# sistema_min.net
KiCad netlist of a schematic drawn in EAGLE
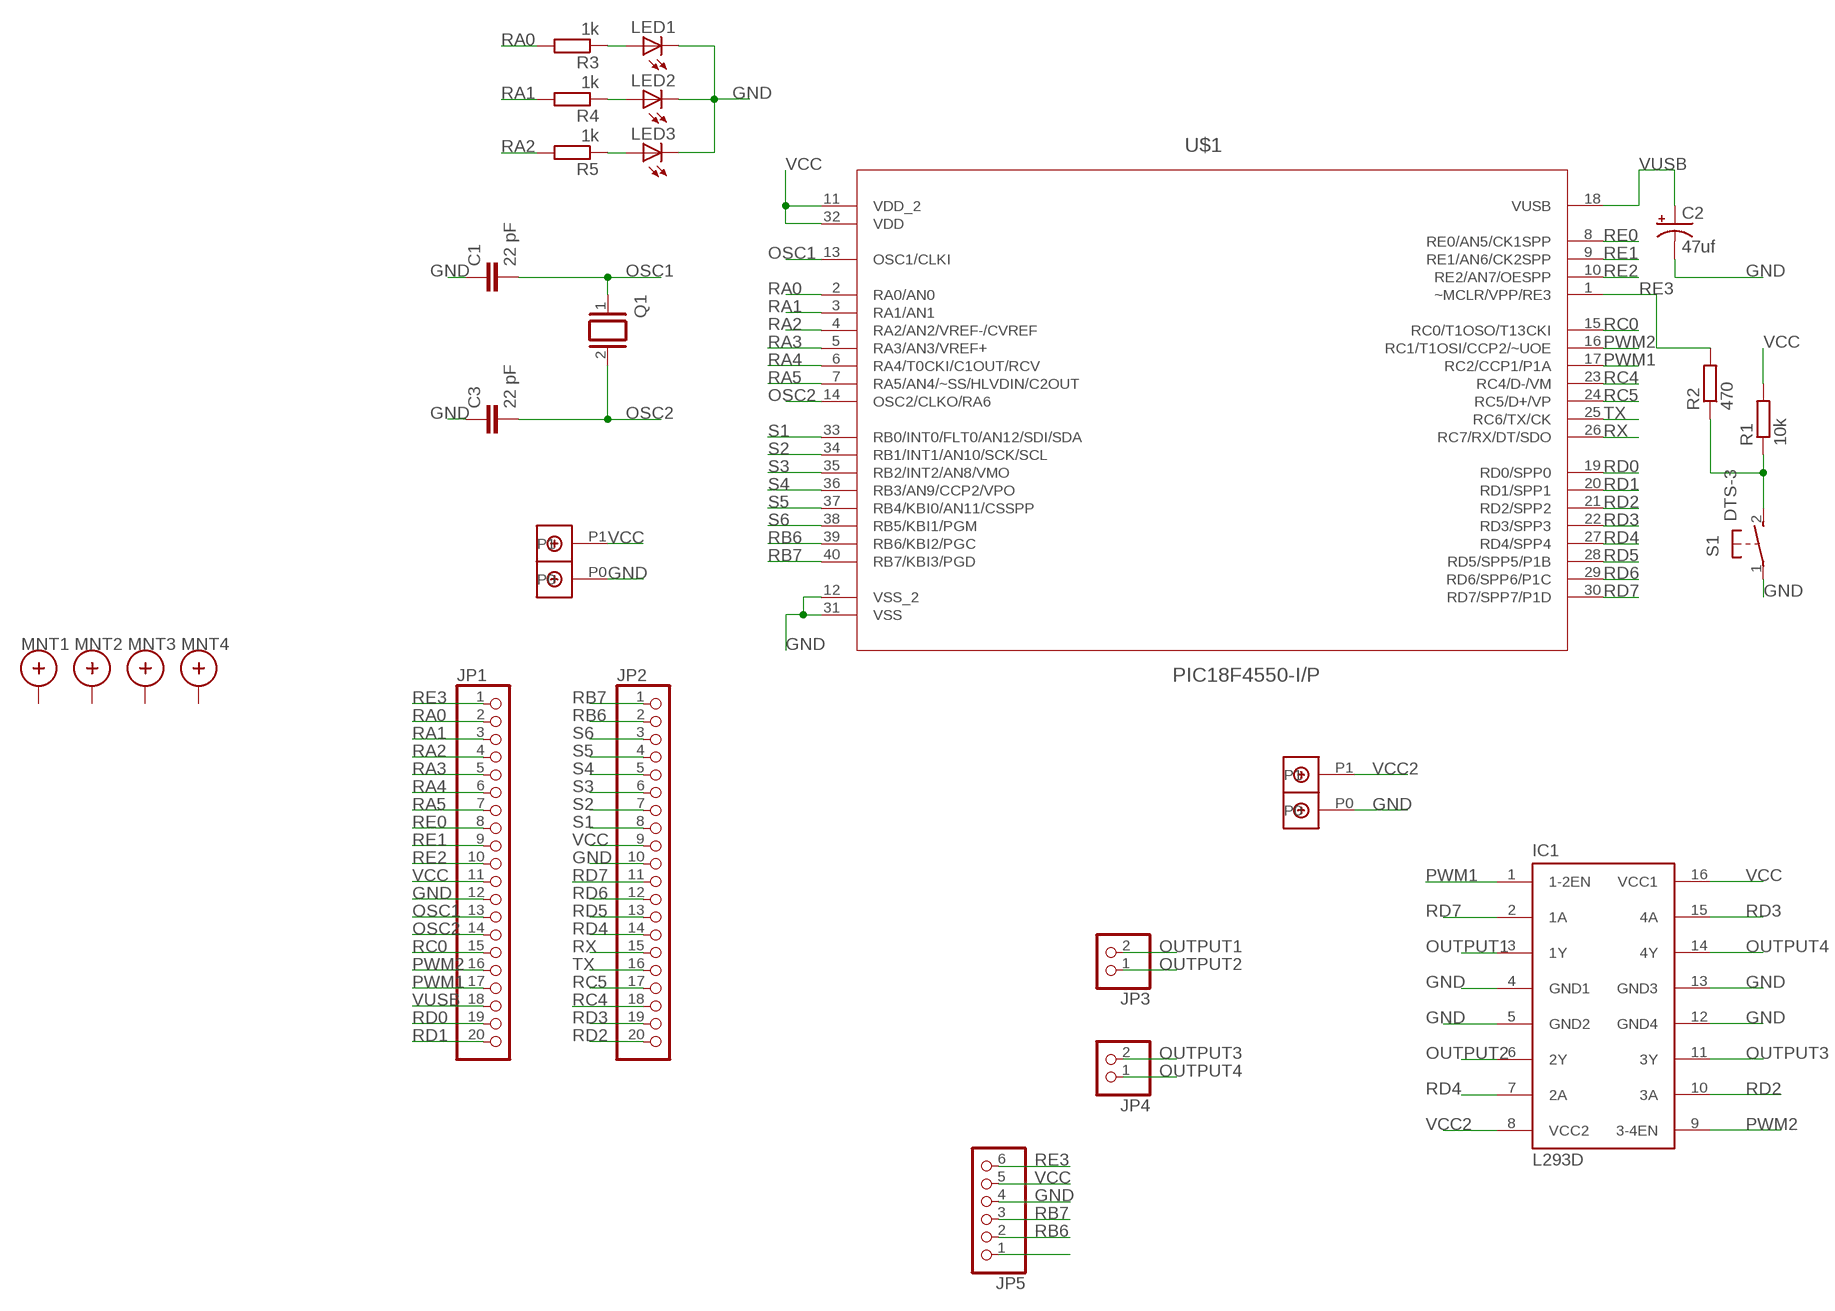
[diagram p0: schematic, sheet 1]

(export (version "E")
  (design (tool "Eeschema 10.0.6"))
  (components
    (comp (ref "C1")
      (value "22 pF")
      (footprint "eagle-import:C050-025X075")
      (libsource (lib "eagle-import") (part "C-EU050-025X075"))
    )
    (comp (ref "C2")
      (value "47uf")
      (footprint "eagle-import:E5-10,5")
      (libsource (lib "eagle-import") (part "CPOL-USE5-10.5"))
    )
    (comp (ref "C3")
      (value "22 pF")
      (footprint "eagle-import:C050-025X075")
      (libsource (lib "eagle-import") (part "C-EU050-025X075"))
    )
    (comp (ref "IC1")
      (value "L293D")
      (footprint "eagle-import:DIL16")
      (libsource (lib "eagle-import") (part "L293D"))
    )
    (comp (ref "JP1")
      (value "PINHD-1X20")
      (footprint "eagle-import:1X20")
      (libsource (lib "eagle-import") (part "PINHD-1X20"))
    )
    (comp (ref "JP2")
      (value "PINHD-1X20")
      (footprint "eagle-import:1X20")
      (libsource (lib "eagle-import") (part "PINHD-1X20"))
    )
    (comp (ref "JP3")
      (value "PINHD-1X2")
      (footprint "eagle-import:1X02")
      (libsource (lib "eagle-import") (part "PINHD-1X2"))
    )
    (comp (ref "JP4")
      (value "PINHD-1X2")
      (footprint "eagle-import:1X02")
      (libsource (lib "eagle-import") (part "PINHD-1X2"))
    )
    (comp (ref "JP5")
      (value "PINHD-1X6")
      (footprint "eagle-import:1X06")
      (libsource (lib "eagle-import") (part "PINHD-1X6"))
    )
    (comp (ref "LED1")
      (value "LED3MM")
      (footprint "eagle-import:LED3MM")
      (libsource (lib "eagle-import") (part "LED3MM"))
    )
    (comp (ref "LED2")
      (value "LED3MM")
      (footprint "eagle-import:LED3MM")
      (libsource (lib "eagle-import") (part "LED3MM"))
    )
    (comp (ref "LED3")
      (value "LED3MM")
      (footprint "eagle-import:LED3MM")
      (libsource (lib "eagle-import") (part "LED3MM"))
    )
    (comp (ref "MNT1")
      (value "HOLE_MNT_0.135")
      (footprint "eagle-import:HOLE_MNT_#5-40")
      (libsource (lib "eagle-import") (part "HOLE_MNT_0.135"))
    )
    (comp (ref "MNT2")
      (value "HOLE_MNT_0.135")
      (footprint "eagle-import:HOLE_MNT_#5-40")
      (libsource (lib "eagle-import") (part "HOLE_MNT_0.135"))
    )
    (comp (ref "MNT3")
      (value "HOLE_MNT_0.135")
      (footprint "eagle-import:HOLE_MNT_#5-40")
      (libsource (lib "eagle-import") (part "HOLE_MNT_0.135"))
    )
    (comp (ref "MNT4")
      (value "HOLE_MNT_0.135")
      (footprint "eagle-import:HOLE_MNT_#5-40")
      (libsource (lib "eagle-import") (part "HOLE_MNT_0.135"))
    )
    (comp (ref "Q1")
      (value "XTAL/S")
      (footprint "eagle-import:QS")
      (libsource (lib "eagle-import") (part "XTAL/S"))
    )
    (comp (ref "R1")
      (value "10k")
      (footprint "eagle-import:0204_7")
      (libsource (lib "eagle-import") (part "R-EU_0204/7"))
    )
    (comp (ref "R2")
      (value "470")
      (footprint "eagle-import:0204_7")
      (libsource (lib "eagle-import") (part "R-EU_0204/7"))
    )
    (comp (ref "R3")
      (value "1k")
      (footprint "eagle-import:0204_7")
      (libsource (lib "eagle-import") (part "R-EU_0204/7"))
    )
    (comp (ref "R4")
      (value "1k")
      (footprint "eagle-import:0204_7")
      (libsource (lib "eagle-import") (part "R-EU_0204/7"))
    )
    (comp (ref "R5")
      (value "1k")
      (footprint "eagle-import:0204_7")
      (libsource (lib "eagle-import") (part "R-EU_0204/7"))
    )
    (comp (ref "S1")
      (value "DTS-3")
      (footprint "eagle-import:DTS-3")
      (libsource (lib "eagle-import") (part "DTS-3"))
    )
    (comp (ref "U$1")
      (value "PIC18F4550-I/P")
      (footprint "eagle-import:DIP254P1524X635-40")
      (libsource (lib "eagle-import") (part "PIC18F4550-I/P"))
    )
    (comp (ref "U$2")
      (value "DBCONN-1X2")
      (footprint "eagle-import:DBCONN-1X2")
      (libsource (lib "eagle-import") (part "DBCONN-1X2"))
    )
    (comp (ref "U$3")
      (value "DBCONN-1X2")
      (footprint "eagle-import:DBCONN-1X2")
      (libsource (lib "eagle-import") (part "DBCONN-1X2"))
    )
  )
  (nets
    (net (code "1") (name "/GND") (class "Default")
      (node (ref "C1") (pin "1") (pinfunction "1_1") (pintype "passive"))
      (node (ref "C2") (pin "-") (pinfunction "-_-") (pintype "passive"))
      (node (ref "C3") (pin "1") (pinfunction "1_1") (pintype "passive"))
      (node (ref "IC1") (pin "12") (pinfunction "GND4_12") (pintype "power_in"))
      (node (ref "IC1") (pin "13") (pinfunction "GND3_13") (pintype "power_in"))
      (node (ref "IC1") (pin "4") (pinfunction "GND1_4") (pintype "power_in"))
      (node (ref "IC1") (pin "5") (pinfunction "GND2_5") (pintype "power_in"))
      (node (ref "JP1") (pin "12") (pinfunction "12_12") (pintype "passive"))
      (node (ref "JP2") (pin "10") (pinfunction "10_10") (pintype "passive"))
      (node (ref "JP5") (pin "4") (pinfunction "4_4") (pintype "passive"))
      (node (ref "LED1") (pin "K") (pinfunction "C_K") (pintype "passive"))
      (node (ref "LED2") (pin "K") (pinfunction "C_K") (pintype "passive"))
      (node (ref "LED3") (pin "K") (pinfunction "C_K") (pintype "passive"))
      (node (ref "S1") (pin "1") (pinfunction "1_1") (pintype "passive"))
      (node (ref "U$1") (pin "12") (pinfunction "VSS_2_12") (pintype "power_in"))
      (node (ref "U$1") (pin "31") (pinfunction "VSS_31") (pintype "power_in"))
      (node (ref "U$2") (pin "P0") (pinfunction "P0_P0") (pintype "bidirectional"))
      (node (ref "U$3") (pin "P0") (pinfunction "P0_P0") (pintype "bidirectional"))
    )
    (net (code "2") (name "/OSC1") (class "Default")
      (node (ref "C1") (pin "2") (pinfunction "2_2") (pintype "passive"))
      (node (ref "JP1") (pin "13") (pinfunction "13_13") (pintype "passive"))
      (node (ref "Q1") (pin "1") (pinfunction "1_1") (pintype "passive"))
      (node (ref "U$1") (pin "13") (pinfunction "OSC1/CLKI_13") (pintype "input"))
    )
    (net (code "3") (name "/OSC2") (class "Default")
      (node (ref "C3") (pin "2") (pinfunction "2_2") (pintype "passive"))
      (node (ref "JP1") (pin "14") (pinfunction "14_14") (pintype "passive"))
      (node (ref "Q1") (pin "2") (pinfunction "2_2") (pintype "passive"))
      (node (ref "U$1") (pin "14") (pinfunction "OSC2/CLKO/RA6_14") (pintype "bidirectional"))
    )
    (net (code "4") (name "/OUTPUT1") (class "Default")
      (node (ref "IC1") (pin "3") (pinfunction "1Y_3") (pintype "output"))
      (node (ref "JP3") (pin "2") (pinfunction "2_2") (pintype "passive"))
    )
    (net (code "5") (name "/OUTPUT2") (class "Default")
      (node (ref "IC1") (pin "6") (pinfunction "2Y_6") (pintype "output"))
      (node (ref "JP3") (pin "1") (pinfunction "1_1") (pintype "passive"))
    )
    (net (code "6") (name "/OUTPUT3") (class "Default")
      (node (ref "IC1") (pin "11") (pinfunction "3Y_11") (pintype "output"))
      (node (ref "JP4") (pin "2") (pinfunction "2_2") (pintype "passive"))
    )
    (net (code "7") (name "/OUTPUT4") (class "Default")
      (node (ref "IC1") (pin "14") (pinfunction "4Y_14") (pintype "output"))
      (node (ref "JP4") (pin "1") (pinfunction "1_1") (pintype "passive"))
    )
    (net (code "8") (name "/PWM1") (class "Default")
      (node (ref "IC1") (pin "1") (pinfunction "1-2EN_1") (pintype "input"))
      (node (ref "JP1") (pin "17") (pinfunction "17_17") (pintype "passive"))
      (node (ref "U$1") (pin "17") (pinfunction "RC2/CCP1/P1A_17") (pintype "bidirectional"))
    )
    (net (code "9") (name "/PWM2") (class "Default")
      (node (ref "IC1") (pin "9") (pinfunction "3-4EN_9") (pintype "input"))
      (node (ref "JP1") (pin "16") (pinfunction "16_16") (pintype "passive"))
      (node (ref "U$1") (pin "16") (pinfunction "RC1/T1OSI/CCP2/~{UOE}_16") (pintype "bidirectional"))
    )
    (net (code "10") (name "/RA0") (class "Default")
      (node (ref "JP1") (pin "2") (pinfunction "2_2") (pintype "passive"))
      (node (ref "R3") (pin "2") (pinfunction "2_2") (pintype "passive"))
      (node (ref "U$1") (pin "2") (pinfunction "RA0/AN0_2") (pintype "bidirectional"))
    )
    (net (code "11") (name "/RA1") (class "Default")
      (node (ref "JP1") (pin "3") (pinfunction "3_3") (pintype "passive"))
      (node (ref "R4") (pin "2") (pinfunction "2_2") (pintype "passive"))
      (node (ref "U$1") (pin "3") (pinfunction "RA1/AN1_3") (pintype "bidirectional"))
    )
    (net (code "12") (name "/RA2") (class "Default")
      (node (ref "JP1") (pin "4") (pinfunction "4_4") (pintype "passive"))
      (node (ref "R5") (pin "2") (pinfunction "2_2") (pintype "passive"))
      (node (ref "U$1") (pin "4") (pinfunction "RA2/AN2/VREF-/CVREF_4") (pintype "bidirectional"))
    )
    (net (code "13") (name "/RA3") (class "Default")
      (node (ref "JP1") (pin "5") (pinfunction "5_5") (pintype "passive"))
      (node (ref "U$1") (pin "5") (pinfunction "RA3/AN3/VREF+_5") (pintype "bidirectional"))
    )
    (net (code "14") (name "/RA4") (class "Default")
      (node (ref "JP1") (pin "6") (pinfunction "6_6") (pintype "passive"))
      (node (ref "U$1") (pin "6") (pinfunction "RA4/T0CKI/C1OUT/RCV_6") (pintype "bidirectional"))
    )
    (net (code "15") (name "/RA5") (class "Default")
      (node (ref "JP1") (pin "7") (pinfunction "7_7") (pintype "passive"))
      (node (ref "U$1") (pin "7") (pinfunction "RA5/AN4/~{SS/HLVDIN/C2OUT}_7") (pintype "bidirectional"))
    )
    (net (code "16") (name "/RB6") (class "Default")
      (node (ref "JP2") (pin "2") (pinfunction "2_2") (pintype "passive"))
      (node (ref "JP5") (pin "2") (pinfunction "2_2") (pintype "passive"))
      (node (ref "U$1") (pin "39") (pinfunction "RB6/KBI2/PGC_39") (pintype "bidirectional"))
    )
    (net (code "17") (name "/RB7") (class "Default")
      (node (ref "JP2") (pin "1") (pinfunction "1_1") (pintype "passive"))
      (node (ref "JP5") (pin "3") (pinfunction "3_3") (pintype "passive"))
      (node (ref "U$1") (pin "40") (pinfunction "RB7/KBI3/PGD_40") (pintype "bidirectional"))
    )
    (net (code "18") (name "/RC0") (class "Default")
      (node (ref "JP1") (pin "15") (pinfunction "15_15") (pintype "passive"))
      (node (ref "U$1") (pin "15") (pinfunction "RC0/T1OSO/T13CKI_15") (pintype "bidirectional"))
    )
    (net (code "19") (name "/RC4") (class "Default")
      (node (ref "JP2") (pin "18") (pinfunction "18_18") (pintype "passive"))
      (node (ref "U$1") (pin "23") (pinfunction "RC4/D-/VM_23") (pintype "bidirectional"))
    )
    (net (code "20") (name "/RC5") (class "Default")
      (node (ref "JP2") (pin "17") (pinfunction "17_17") (pintype "passive"))
      (node (ref "U$1") (pin "24") (pinfunction "RC5/D+/VP_24") (pintype "bidirectional"))
    )
    (net (code "21") (name "/RD0") (class "Default")
      (node (ref "JP1") (pin "19") (pinfunction "19_19") (pintype "passive"))
      (node (ref "U$1") (pin "19") (pinfunction "RD0/SPP0_19") (pintype "bidirectional"))
    )
    (net (code "22") (name "/RD1") (class "Default")
      (node (ref "JP1") (pin "20") (pinfunction "20_20") (pintype "passive"))
      (node (ref "U$1") (pin "20") (pinfunction "RD1/SPP1_20") (pintype "bidirectional"))
    )
    (net (code "23") (name "/RD2") (class "Default")
      (node (ref "IC1") (pin "10") (pinfunction "3A_10") (pintype "input"))
      (node (ref "JP2") (pin "20") (pinfunction "20_20") (pintype "passive"))
      (node (ref "U$1") (pin "21") (pinfunction "RD2/SPP2_21") (pintype "bidirectional"))
    )
    (net (code "24") (name "/RD3") (class "Default")
      (node (ref "IC1") (pin "15") (pinfunction "4A_15") (pintype "input"))
      (node (ref "JP2") (pin "19") (pinfunction "19_19") (pintype "passive"))
      (node (ref "U$1") (pin "22") (pinfunction "RD3/SPP3_22") (pintype "bidirectional"))
    )
    (net (code "25") (name "/RD4") (class "Default")
      (node (ref "IC1") (pin "7") (pinfunction "2A_7") (pintype "input"))
      (node (ref "JP2") (pin "14") (pinfunction "14_14") (pintype "passive"))
      (node (ref "U$1") (pin "27") (pinfunction "RD4/SPP4_27") (pintype "bidirectional"))
    )
    (net (code "26") (name "/RD5") (class "Default")
      (node (ref "JP2") (pin "13") (pinfunction "13_13") (pintype "passive"))
      (node (ref "U$1") (pin "28") (pinfunction "RD5/SPP5/P1B_28") (pintype "bidirectional"))
    )
    (net (code "27") (name "/RD6") (class "Default")
      (node (ref "JP2") (pin "12") (pinfunction "12_12") (pintype "passive"))
      (node (ref "U$1") (pin "29") (pinfunction "RD6/SPP6/P1C_29") (pintype "bidirectional"))
    )
    (net (code "28") (name "/RD7") (class "Default")
      (node (ref "IC1") (pin "2") (pinfunction "1A_2") (pintype "input"))
      (node (ref "JP2") (pin "11") (pinfunction "11_11") (pintype "passive"))
      (node (ref "U$1") (pin "30") (pinfunction "RD7/SPP7/P1D_30") (pintype "bidirectional"))
    )
    (net (code "29") (name "/RE0") (class "Default")
      (node (ref "JP1") (pin "8") (pinfunction "8_8") (pintype "passive"))
      (node (ref "U$1") (pin "8") (pinfunction "RE0/AN5/CK1SPP_8") (pintype "bidirectional"))
    )
    (net (code "30") (name "/RE1") (class "Default")
      (node (ref "JP1") (pin "9") (pinfunction "9_9") (pintype "passive"))
      (node (ref "U$1") (pin "9") (pinfunction "RE1/AN6/CK2SPP_9") (pintype "bidirectional"))
    )
    (net (code "31") (name "/RE2") (class "Default")
      (node (ref "JP1") (pin "10") (pinfunction "10_10") (pintype "passive"))
      (node (ref "U$1") (pin "10") (pinfunction "RE2/AN7/OESPP_10") (pintype "bidirectional"))
    )
    (net (code "32") (name "/RE3") (class "Default")
      (node (ref "JP1") (pin "1") (pinfunction "1_1") (pintype "passive"))
      (node (ref "JP5") (pin "6") (pinfunction "6_6") (pintype "passive"))
      (node (ref "R2") (pin "2") (pinfunction "2_2") (pintype "passive"))
      (node (ref "U$1") (pin "1") (pinfunction "~{MCLR/VPP/RE3}_1") (pintype "input"))
    )
    (net (code "33") (name "/RX") (class "Default")
      (node (ref "JP2") (pin "15") (pinfunction "15_15") (pintype "passive"))
      (node (ref "U$1") (pin "26") (pinfunction "RC7/RX/DT/SDO_26") (pintype "bidirectional"))
    )
    (net (code "34") (name "/S1") (class "Default")
      (node (ref "JP2") (pin "8") (pinfunction "8_8") (pintype "passive"))
      (node (ref "U$1") (pin "33") (pinfunction "RB0/INT0/FLT0/AN12/SDI/SDA_33") (pintype "bidirectional"))
    )
    (net (code "35") (name "/S2") (class "Default")
      (node (ref "JP2") (pin "7") (pinfunction "7_7") (pintype "passive"))
      (node (ref "U$1") (pin "34") (pinfunction "RB1/INT1/AN10/SCK/SCL_34") (pintype "bidirectional"))
    )
    (net (code "36") (name "/S3") (class "Default")
      (node (ref "JP2") (pin "6") (pinfunction "6_6") (pintype "passive"))
      (node (ref "U$1") (pin "35") (pinfunction "RB2/INT2/AN8/VMO_35") (pintype "bidirectional"))
    )
    (net (code "37") (name "/S4") (class "Default")
      (node (ref "JP2") (pin "5") (pinfunction "5_5") (pintype "passive"))
      (node (ref "U$1") (pin "36") (pinfunction "RB3/AN9/CCP2/VPO_36") (pintype "bidirectional"))
    )
    (net (code "38") (name "/S5") (class "Default")
      (node (ref "JP2") (pin "4") (pinfunction "4_4") (pintype "passive"))
      (node (ref "U$1") (pin "37") (pinfunction "RB4/KBI0/AN11/CSSPP_37") (pintype "bidirectional"))
    )
    (net (code "39") (name "/S6") (class "Default")
      (node (ref "JP2") (pin "3") (pinfunction "3_3") (pintype "passive"))
      (node (ref "U$1") (pin "38") (pinfunction "RB5/KBI1/PGM_38") (pintype "bidirectional"))
    )
    (net (code "40") (name "/TX") (class "Default")
      (node (ref "JP2") (pin "16") (pinfunction "16_16") (pintype "passive"))
      (node (ref "U$1") (pin "25") (pinfunction "RC6/TX/CK_25") (pintype "bidirectional"))
    )
    (net (code "41") (name "/VCC") (class "Default")
      (node (ref "IC1") (pin "16") (pinfunction "VCC1_16") (pintype "power_in"))
      (node (ref "JP1") (pin "11") (pinfunction "11_11") (pintype "passive"))
      (node (ref "JP2") (pin "9") (pinfunction "9_9") (pintype "passive"))
      (node (ref "JP5") (pin "5") (pinfunction "5_5") (pintype "passive"))
      (node (ref "R1") (pin "2") (pinfunction "2_2") (pintype "passive"))
      (node (ref "U$1") (pin "11") (pinfunction "VDD_2_11") (pintype "power_in"))
      (node (ref "U$1") (pin "32") (pinfunction "VDD_32") (pintype "power_in"))
      (node (ref "U$2") (pin "P1") (pinfunction "P1_P1") (pintype "bidirectional"))
    )
    (net (code "42") (name "/VCC2") (class "Default")
      (node (ref "IC1") (pin "8") (pinfunction "VCC2_8") (pintype "power_in"))
      (node (ref "U$3") (pin "P1") (pinfunction "P1_P1") (pintype "bidirectional"))
    )
    (net (code "43") (name "/VUSB") (class "Default")
      (node (ref "C2") (pin "+") (pinfunction "+_+") (pintype "passive"))
      (node (ref "JP1") (pin "18") (pinfunction "18_18") (pintype "passive"))
      (node (ref "U$1") (pin "18") (pinfunction "VUSB_18") (pintype "bidirectional"))
    )
    (net (code "44") (name "Net-(LED1-PadA)") (class "Default")
      (node (ref "LED1") (pin "A") (pinfunction "A_A") (pintype "passive"))
      (node (ref "R3") (pin "1") (pinfunction "1_1") (pintype "passive"))
    )
    (net (code "45") (name "Net-(LED2-PadA)") (class "Default")
      (node (ref "LED2") (pin "A") (pinfunction "A_A") (pintype "passive"))
      (node (ref "R4") (pin "1") (pinfunction "1_1") (pintype "passive"))
    )
    (net (code "46") (name "Net-(LED3-PadA)") (class "Default")
      (node (ref "LED3") (pin "A") (pinfunction "A_A") (pintype "passive"))
      (node (ref "R5") (pin "1") (pinfunction "1_1") (pintype "passive"))
    )
    (net (code "47") (name "Net-(R1-Pad1)") (class "Default")
      (node (ref "R1") (pin "1") (pinfunction "1_1") (pintype "passive"))
      (node (ref "R2") (pin "1") (pinfunction "1_1") (pintype "passive"))
      (node (ref "S1") (pin "2") (pinfunction "2_2") (pintype "passive"))
    )
    (net (code "48") (name "unconnected-(JP5-Pad1)") (class "Default")
      (node (ref "JP5") (pin "1") (pinfunction "1_1") (pintype "passive"))
    )
    (net (code "49") (name "unconnected-(MNT1-1-PadP$1)") (class "Default")
      (node (ref "MNT1") (pin "P$1") (pinfunction "1_P$1") (pintype "bidirectional"))
    )
    (net (code "50") (name "unconnected-(MNT2-1-PadP$1)") (class "Default")
      (node (ref "MNT2") (pin "P$1") (pinfunction "1_P$1") (pintype "bidirectional"))
    )
    (net (code "51") (name "unconnected-(MNT3-1-PadP$1)") (class "Default")
      (node (ref "MNT3") (pin "P$1") (pinfunction "1_P$1") (pintype "bidirectional"))
    )
    (net (code "52") (name "unconnected-(MNT4-1-PadP$1)") (class "Default")
      (node (ref "MNT4") (pin "P$1") (pinfunction "1_P$1") (pintype "bidirectional"))
    )
  )
)
